# Power.net
KiCad netlist of a schematic drawn in Altium Designer
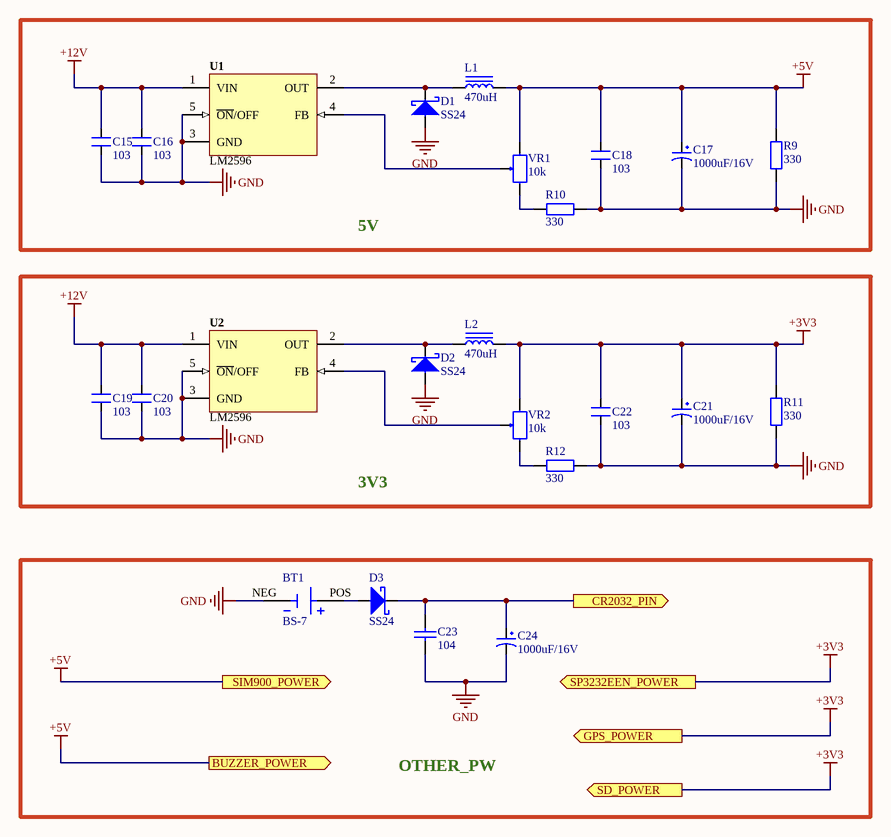
[diagram p0: Power.SchDoc]

(export (version "E")
  (design (tool "Eeschema 10.0.6"))
  (components
    (comp (ref "BT1")
      (value "BS-7")
      (footprint "BAT_BS-7")
      (description "Battery Holder (Open) Coin, 20.0mm 1 Cell PC Pin")
      (fields (field (name "MF") "MPD (Memory") (field (name "DIGI-KEY_PART_NUMBER") "BS-7-ND"))
      (libsource (lib "CR_BATTERY") (part "BS-7"))
    )
    (comp (ref "C15")
      (value "103")
      (footprint "SM-0805")
      (description "Cap SMD")
      (libsource (lib "KhanhBK_Library_4") (part "CM"))
    )
    (comp (ref "C16")
      (value "103")
      (footprint "SM-0603")
      (description "Cap SMD")
      (libsource (lib "KhanhBK_Library_4") (part "CM"))
    )
    (comp (ref "C17")
      (value "1000uF/16V")
      (footprint "CP1.5/3.4")
      (description "Cap 1000uF/16V - 220uF/50V")
      (libsource (lib "KhanhBK_Library_4") (part "CP4"))
    )
    (comp (ref "C18")
      (value "103")
      (footprint "SM-0603")
      (description "Cap SMD")
      (libsource (lib "KhanhBK_Library_4") (part "CM"))
    )
    (comp (ref "C19")
      (value "103")
      (footprint "SM-0805")
      (description "Cap SMD")
      (libsource (lib "KhanhBK_Library_4") (part "CM"))
    )
    (comp (ref "C20")
      (value "103")
      (footprint "SM-0603")
      (description "Cap SMD")
      (libsource (lib "KhanhBK_Library_4") (part "CM"))
    )
    (comp (ref "C21")
      (value "1000uF/16V")
      (footprint "CP1.5/3.4")
      (description "Cap 1000uF/16V - 220uF/50V")
      (libsource (lib "KhanhBK_Library_4") (part "CP4"))
    )
    (comp (ref "C22")
      (value "103")
      (footprint "SM-0603")
      (description "Cap SMD")
      (libsource (lib "KhanhBK_Library_4") (part "CM"))
    )
    (comp (ref "C23")
      (value "104")
      (footprint "0805")
      (description "Capacitor (Semiconductor SIM Model)")
      (fields (field (name "PUBLISHER") "Altium Limited"))
      (libsource (lib "Devzone_SCHLib") (part "Cap 104_SMD"))
    )
    (comp (ref "C24")
      (value "1000uF/16V")
      (footprint "CP1.5/3.4")
      (description "Cap 1000uF/16V - 220uF/50V")
      (libsource (lib "KhanhBK_Library_4") (part "CP4"))
    )
    (comp (ref "D1")
      (value "SS24")
      (footprint "DIO-SMD-106")
      (description "Diode Schottky")
      (fields (field (name "PART NUMBER") "LED 3 ly Single Colour"))
      (libsource (lib "KhanhBK_Library_4") (part "Diode Schottky"))
    )
    (comp (ref "D2")
      (value "SS24")
      (footprint "DIO-SMD-106")
      (description "Diode Schottky")
      (fields (field (name "PART NUMBER") "LED 3 ly Single Colour"))
      (libsource (lib "KhanhBK_Library_4") (part "Diode Schottky"))
    )
    (comp (ref "D3")
      (value "SS24")
      (footprint "DIO-SMD-106")
      (description "Diode Schottky")
      (fields (field (name "PART NUMBER") "LED 3 ly Single Colour"))
      (libsource (lib "KhanhBK_Library_4") (part "Diode Schottky"))
    )
    (comp (ref "L1")
      (value "470uH")
      (footprint "BOURNS SRR1280")
      (description "SMT Inductor")
      (libsource (lib "KhanhBK_Library_4") (part "Inductor"))
    )
    (comp (ref "L2")
      (value "470uH")
      (footprint "BOURNS SRR1280")
      (description "SMT Inductor")
      (libsource (lib "KhanhBK_Library_4") (part "Inductor"))
    )
    (comp (ref "R9")
      (value "330")
      (footprint "RES-1/4W")
      (description "Resistor R1/4W")
      (libsource (lib "KhanhBK_Library_4") (part "R"))
    )
    (comp (ref "R10")
      (value "330")
      (footprint "RES-1/4W")
      (description "Resistor R1/4W")
      (libsource (lib "KhanhBK_Library_4") (part "R"))
    )
    (comp (ref "R11")
      (value "330")
      (footprint "RES-1/4W")
      (description "Resistor R1/4W")
      (libsource (lib "KhanhBK_Library_4") (part "R"))
    )
    (comp (ref "R12")
      (value "330")
      (footprint "RES-1/4W")
      (description "Resistor R1/4W")
      (libsource (lib "KhanhBK_Library_4") (part "R"))
    )
    (comp (ref "U1")
      (value "LM2596")
      (footprint "TO263")
      (libsource (lib "KhanhBK_SCH_Library_2") (part "LM2596"))
    )
    (comp (ref "U2")
      (value "LM2596")
      (footprint "TO263")
      (libsource (lib "KhanhBK_SCH_Library_2") (part "LM2596"))
    )
    (comp (ref "VR1")
      (value "10k")
      (footprint "VR-S3")
      (libsource (lib "KhanhBK_Library_4") (part "Resistor Var"))
    )
    (comp (ref "VR2")
      (value "10k")
      (footprint "VR-S3")
      (libsource (lib "KhanhBK_Library_4") (part "Resistor Var"))
    )
  )
  (nets
    (net (code "1") (name "+3V3") (class "Default")
      (node (ref "C21") (pin "1") (pinfunction "1_1") (pintype "passive"))
      (node (ref "C22") (pin "2") (pinfunction "2_2") (pintype "passive"))
      (node (ref "L2") (pin "2") (pinfunction "2_2") (pintype "passive"))
      (node (ref "R11") (pin "2") (pinfunction "2_2") (pintype "passive"))
      (node (ref "VR2") (pin "3") (pinfunction "3_3") (pintype "passive"))
    )
    (net (code "2") (name "+5V") (class "Default")
      (node (ref "C17") (pin "1") (pinfunction "1_1") (pintype "passive"))
      (node (ref "C18") (pin "2") (pinfunction "2_2") (pintype "passive"))
      (node (ref "L1") (pin "2") (pinfunction "2_2") (pintype "passive"))
      (node (ref "R9") (pin "2") (pinfunction "2_2") (pintype "passive"))
      (node (ref "VR1") (pin "3") (pinfunction "3_3") (pintype "passive"))
    )
    (net (code "3") (name "+12V") (class "Default")
      (node (ref "C15") (pin "2") (pinfunction "2_2") (pintype "passive"))
      (node (ref "C16") (pin "2") (pinfunction "2_2") (pintype "passive"))
      (node (ref "C19") (pin "2") (pinfunction "2_2") (pintype "passive"))
      (node (ref "C20") (pin "2") (pinfunction "2_2") (pintype "passive"))
      (node (ref "U1") (pin "1") (pinfunction "VIN_1") (pintype "power_in"))
      (node (ref "U2") (pin "1") (pinfunction "VIN_1") (pintype "power_in"))
    )
    (net (code "4") (name "/CR2032_PIN") (class "Default")
      (node (ref "C23") (pin "2") (pintype "passive"))
      (node (ref "C24") (pin "1") (pinfunction "1_1") (pintype "passive"))
      (node (ref "D3") (pin "2") (pinfunction "2_2") (pintype "passive"))
    )
    (net (code "5") (name "GND") (class "Default")
      (node (ref "BT1") (pin "NEG") (pinfunction "NEG_NEG") (pintype "passive"))
      (node (ref "C15") (pin "1") (pinfunction "1_1") (pintype "passive"))
      (node (ref "C16") (pin "1") (pinfunction "1_1") (pintype "passive"))
      (node (ref "C17") (pin "2") (pinfunction "2_2") (pintype "passive"))
      (node (ref "C18") (pin "1") (pinfunction "1_1") (pintype "passive"))
      (node (ref "C19") (pin "1") (pinfunction "1_1") (pintype "passive"))
      (node (ref "C20") (pin "1") (pinfunction "1_1") (pintype "passive"))
      (node (ref "C21") (pin "2") (pinfunction "2_2") (pintype "passive"))
      (node (ref "C22") (pin "1") (pinfunction "1_1") (pintype "passive"))
      (node (ref "C23") (pin "1") (pintype "passive"))
      (node (ref "C24") (pin "2") (pinfunction "2_2") (pintype "passive"))
      (node (ref "D1") (pin "1") (pinfunction "1_1") (pintype "passive"))
      (node (ref "D2") (pin "1") (pinfunction "1_1") (pintype "passive"))
      (node (ref "R10") (pin "1") (pinfunction "1_1") (pintype "passive"))
      (node (ref "R11") (pin "1") (pinfunction "1_1") (pintype "passive"))
      (node (ref "R12") (pin "1") (pinfunction "1_1") (pintype "passive"))
      (node (ref "R9") (pin "1") (pinfunction "1_1") (pintype "passive"))
      (node (ref "U1") (pin "3") (pinfunction "GND_3") (pintype "power_in"))
      (node (ref "U1") (pin "5") (pinfunction "~{ON}/OFF_5") (pintype "input"))
      (node (ref "U2") (pin "3") (pinfunction "GND_3") (pintype "power_in"))
      (node (ref "U2") (pin "5") (pinfunction "~{ON}/OFF_5") (pintype "input"))
    )
    (net (code "6") (name "Net-(BT1-PadPOS)") (class "Default")
      (node (ref "BT1") (pin "POS") (pinfunction "POS_POS") (pintype "passive"))
      (node (ref "D3") (pin "1") (pinfunction "1_1") (pintype "passive"))
    )
    (net (code "7") (name "Net-(R10-Pad2)") (class "Default")
      (node (ref "R10") (pin "2") (pinfunction "2_2") (pintype "passive"))
      (node (ref "VR1") (pin "1") (pinfunction "1_1") (pintype "passive"))
    )
    (net (code "8") (name "Net-(R12-Pad2)") (class "Default")
      (node (ref "R12") (pin "2") (pinfunction "2_2") (pintype "passive"))
      (node (ref "VR2") (pin "1") (pinfunction "1_1") (pintype "passive"))
    )
    (net (code "9") (name "Net-(U1-FB)") (class "Default")
      (node (ref "U1") (pin "4") (pinfunction "FB_4") (pintype "input"))
      (node (ref "VR1") (pin "2") (pinfunction "2_2") (pintype "passive"))
    )
    (net (code "10") (name "Net-(U1-OUT)") (class "Default")
      (node (ref "D1") (pin "2") (pinfunction "2_2") (pintype "passive"))
      (node (ref "L1") (pin "1") (pinfunction "1_1") (pintype "passive"))
      (node (ref "U1") (pin "2") (pinfunction "OUT_2") (pintype "power_in"))
    )
    (net (code "11") (name "Net-(U2-FB)") (class "Default")
      (node (ref "U2") (pin "4") (pinfunction "FB_4") (pintype "input"))
      (node (ref "VR2") (pin "2") (pinfunction "2_2") (pintype "passive"))
    )
    (net (code "12") (name "Net-(U2-OUT)") (class "Default")
      (node (ref "D2") (pin "2") (pinfunction "2_2") (pintype "passive"))
      (node (ref "L2") (pin "1") (pinfunction "1_1") (pintype "passive"))
      (node (ref "U2") (pin "2") (pinfunction "OUT_2") (pintype "power_in"))
    )
  )
)
